# Leds_pack.net
KiCad netlist of a schematic drawn in Altium Designer
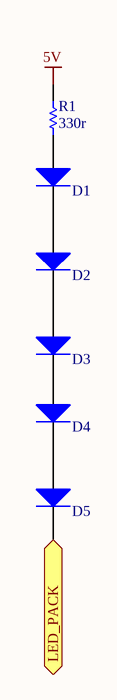
[diagram p0: Leds_pack.SchDoc]

(export (version "E")
  (design (tool "Eeschema 10.0.6"))
  (components
    (comp (ref "D1")
      (value "LED GREEN 2.2V 20mA 3mm")
      (footprint "SMC")
      (description "Default Diode")
      (fields (field (name "PUBLISHER") "Altium Limited"))
      (libsource (lib "Miscellaneous Devices") (part "Diode"))
    )
    (comp (ref "D2")
      (value "LED GREEN 2.2V 20mA 3mm")
      (footprint "SMC")
      (description "Default Diode")
      (fields (field (name "PUBLISHER") "Altium Limited"))
      (libsource (lib "Miscellaneous Devices") (part "Diode"))
    )
    (comp (ref "D3")
      (value "LED GREEN 2.2V 20mA 3mm")
      (footprint "SMC")
      (description "Default Diode")
      (fields (field (name "PUBLISHER") "Altium Limited"))
      (libsource (lib "Miscellaneous Devices") (part "Diode"))
    )
    (comp (ref "D4")
      (value "LED GREEN 2.2V 20mA 3mm")
      (footprint "SMC")
      (description "Default Diode")
      (fields (field (name "PUBLISHER") "Altium Limited"))
      (libsource (lib "Miscellaneous Devices") (part "Diode"))
    )
    (comp (ref "D5")
      (value "LED GREEN 2.2V 20mA 3mm")
      (footprint "SMC")
      (description "Default Diode")
      (fields (field (name "PUBLISHER") "Altium Limited"))
      (libsource (lib "Miscellaneous Devices") (part "Diode"))
    )
    (comp (ref "R1")
      (value "330r")
      (footprint "AXIAL-0.3")
      (description "Resistor")
      (fields (field (name "PUBLISHER") "Altium Limited"))
      (libsource (lib "Miscellaneous Devices") (part "Res1"))
    )
  )
  (nets
    (net (code "1") (name "/LED_PACK") (class "Default")
      (node (ref "D5") (pin "2") (pinfunction "K_2") (pintype "passive"))
    )
    (net (code "2") (name "5V") (class "Default")
      (node (ref "R1") (pin "2") (pinfunction "2_2") (pintype "passive"))
    )
    (net (code "3") (name "Net-(D1-K)") (class "Default")
      (node (ref "D1") (pin "2") (pinfunction "K_2") (pintype "passive"))
      (node (ref "D2") (pin "1") (pinfunction "A_1") (pintype "passive"))
    )
    (net (code "4") (name "Net-(D2-K)") (class "Default")
      (node (ref "D2") (pin "2") (pinfunction "K_2") (pintype "passive"))
      (node (ref "D3") (pin "1") (pinfunction "A_1") (pintype "passive"))
    )
    (net (code "5") (name "Net-(D4-K)") (class "Default")
      (node (ref "D4") (pin "2") (pinfunction "K_2") (pintype "passive"))
      (node (ref "D5") (pin "1") (pinfunction "A_1") (pintype "passive"))
    )
    (net (code "6") (name "unconnected-(D1-A-Pad1)") (class "Default")
      (node (ref "D1") (pin "1") (pinfunction "A_1") (pintype "passive"))
    )
    (net (code "7") (name "unconnected-(D3-K-Pad2)") (class "Default")
      (node (ref "D3") (pin "2") (pinfunction "K_2") (pintype "passive"))
    )
    (net (code "8") (name "unconnected-(D4-A-Pad1)") (class "Default")
      (node (ref "D4") (pin "1") (pinfunction "A_1") (pintype "passive"))
    )
    (net (code "9") (name "unconnected-(R1-Pad1)") (class "Default")
      (node (ref "R1") (pin "1") (pinfunction "1_1") (pintype "passive"))
    )
  )
)
